# headset.net
KiCad netlist of a schematic drawn in EAGLE
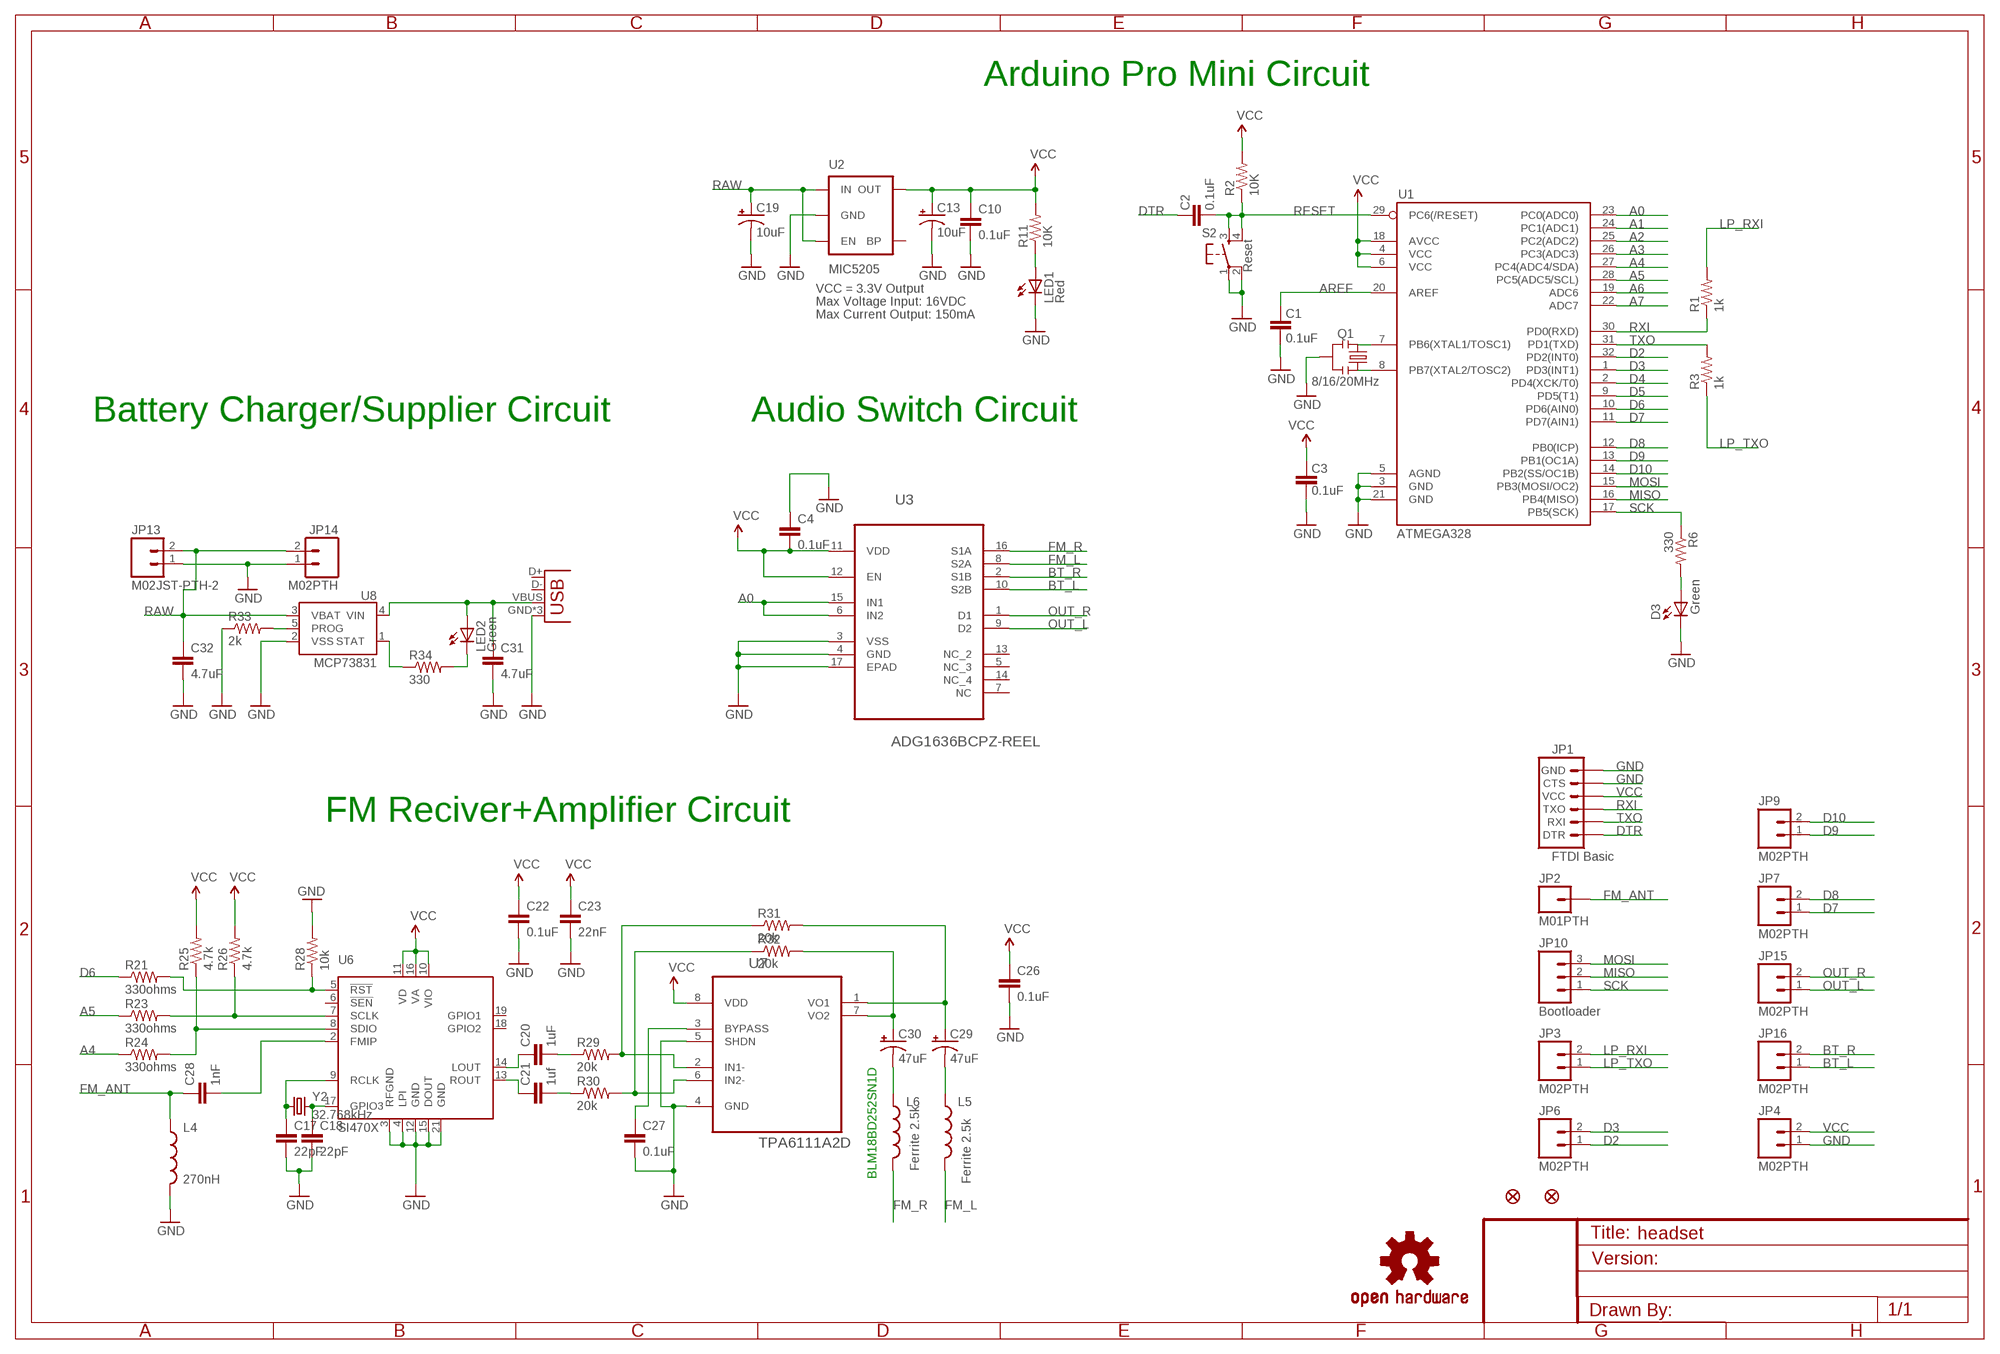
[diagram p0: schematic, sheet 1]

(export (version "E")
  (design (tool "Eeschema 10.0.6"))
  (components
    (comp (ref "C1")
      (value "0.1uF")
      (footprint "eagle-import:0402-CAP")
      (libsource (lib "eagle-import") (part "CAP0402-CAP"))
    )
    (comp (ref "C2")
      (value "0.1uF")
      (footprint "eagle-import:0402-CAP")
      (libsource (lib "eagle-import") (part "CAP0402-CAP"))
    )
    (comp (ref "C3")
      (value "0.1uF")
      (footprint "eagle-import:0402-CAP")
      (libsource (lib "eagle-import") (part "CAP0402-CAP"))
    )
    (comp (ref "C4")
      (value "0.1uF")
      (footprint "eagle-import:0402-CAP")
      (libsource (lib "eagle-import") (part "SparkFun-Passives_CAP0402-CAP"))
    )
    (comp (ref "C10")
      (value "0.1uF")
      (footprint "eagle-import:0402-CAP")
      (libsource (lib "eagle-import") (part "CAP0402-CAP"))
    )
    (comp (ref "C13")
      (value "10uF")
      (footprint "eagle-import:EIA3216")
      (libsource (lib "eagle-import") (part "CAP_POL1206"))
    )
    (comp (ref "C17")
      (value "22pF")
      (footprint "eagle-import:0402-CAP")
      (libsource (lib "eagle-import") (part "SparkFun-Passives_CAP0402-CAP"))
    )
    (comp (ref "C18")
      (value "22pF")
      (footprint "eagle-import:0402-CAP")
      (libsource (lib "eagle-import") (part "SparkFun-Passives_CAP0402-CAP"))
    )
    (comp (ref "C19")
      (value "10uF")
      (footprint "eagle-import:EIA3216")
      (libsource (lib "eagle-import") (part "CAP_POL1206"))
    )
    (comp (ref "C20")
      (value "1uF")
      (footprint "eagle-import:0402-CAP")
      (libsource (lib "eagle-import") (part "SparkFun-Passives_CAP0402-CAP"))
    )
    (comp (ref "C21")
      (value "1uf")
      (footprint "eagle-import:0402-CAP")
      (libsource (lib "eagle-import") (part "SparkFun-Passives_CAP0402-CAP"))
    )
    (comp (ref "C22")
      (value "0.1uF")
      (footprint "eagle-import:0402-CAP")
      (libsource (lib "eagle-import") (part "SparkFun-Passives_CAP0402-CAP"))
    )
    (comp (ref "C23")
      (value "22nF")
      (footprint "eagle-import:0402-CAP")
      (libsource (lib "eagle-import") (part "SparkFun-Passives_CAP0402-CAP"))
    )
    (comp (ref "C26")
      (value "0.1uF")
      (footprint "eagle-import:0402-CAP")
      (libsource (lib "eagle-import") (part "SparkFun-Passives_CAP0402-CAP"))
    )
    (comp (ref "C27")
      (value "0.1uF")
      (footprint "eagle-import:0402-CAP")
      (libsource (lib "eagle-import") (part "SparkFun-Passives_CAP0402-CAP"))
    )
    (comp (ref "C28")
      (value "1nF")
      (footprint "eagle-import:0402-CAP")
      (libsource (lib "eagle-import") (part "SparkFun-Passives_CAP0402-CAP"))
    )
    (comp (ref "C29")
      (value "47uF")
      (footprint "eagle-import:EIA3528")
      (libsource (lib "eagle-import") (part "SparkFun-Passives_CAP_POL3528"))
    )
    (comp (ref "C30")
      (value "47uF")
      (footprint "eagle-import:EIA3528")
      (libsource (lib "eagle-import") (part "SparkFun-Passives_CAP_POL3528"))
    )
    (comp (ref "C31")
      (value "4.7uF")
      (footprint "eagle-import:0402-CAP")
      (libsource (lib "eagle-import") (part "SparkFun-Passives_CAP0402-CAP"))
    )
    (comp (ref "C32")
      (value "4.7uF")
      (footprint "eagle-import:0402-CAP")
      (libsource (lib "eagle-import") (part "SparkFun-Passives_CAP0402-CAP"))
    )
    (comp (ref "D3")
      (value "Green")
      (footprint "eagle-import:LED-0603")
      (libsource (lib "eagle-import") (part "LED0603"))
    )
    (comp (ref "JP1")
      (value "FTDI Basic")
      (footprint "eagle-import:1X06")
      (libsource (lib "eagle-import") (part "ARDUINO_SERIAL_PROGRAMPTH"))
    )
    (comp (ref "JP2")
      (value "M01PTH")
      (footprint "eagle-import:1X01")
      (libsource (lib "eagle-import") (part "M01PTH"))
    )
    (comp (ref "JP3")
      (value "M02PTH")
      (footprint "eagle-import:1X02")
      (libsource (lib "eagle-import") (part "M02PTH"))
    )
    (comp (ref "JP4")
      (value "M02PTH")
      (footprint "eagle-import:1X02")
      (libsource (lib "eagle-import") (part "M02PTH"))
    )
    (comp (ref "JP5")
      (value "FIDUCIALUFIDUCIAL")
      (footprint "eagle-import:MICRO-FIDUCIAL")
      (libsource (lib "eagle-import") (part "FIDUCIALUFIDUCIAL"))
    )
    (comp (ref "JP6")
      (value "M02PTH")
      (footprint "eagle-import:1X02")
      (libsource (lib "eagle-import") (part "M02PTH"))
    )
    (comp (ref "JP7")
      (value "M02PTH")
      (footprint "eagle-import:1X02")
      (libsource (lib "eagle-import") (part "M02PTH"))
    )
    (comp (ref "JP8")
      (value "FIDUCIALUFIDUCIAL")
      (footprint "eagle-import:MICRO-FIDUCIAL")
      (libsource (lib "eagle-import") (part "FIDUCIALUFIDUCIAL"))
    )
    (comp (ref "JP9")
      (value "M02PTH")
      (footprint "eagle-import:1X02")
      (libsource (lib "eagle-import") (part "M02PTH"))
    )
    (comp (ref "JP10")
      (value "Bootloader")
      (footprint "eagle-import:1X03")
      (libsource (lib "eagle-import") (part "M03PTH"))
    )
    (comp (ref "JP12")
      (value "USB-MICROB")
      (footprint "eagle-import:USB-MICROB")
      (libsource (lib "eagle-import") (part "USB-MICROB"))
    )
    (comp (ref "JP13")
      (value "M02JST-PTH-2")
      (footprint "eagle-import:JST-2-PTH")
      (libsource (lib "eagle-import") (part "M02JST-PTH-2"))
    )
    (comp (ref "JP14")
      (value "M02PTH")
      (footprint "eagle-import:1X02")
      (libsource (lib "eagle-import") (part "M02PTH"))
    )
    (comp (ref "JP15")
      (value "M02PTH")
      (footprint "eagle-import:1X02")
      (libsource (lib "eagle-import") (part "M02PTH"))
    )
    (comp (ref "JP16")
      (value "M02PTH")
      (footprint "eagle-import:1X02")
      (libsource (lib "eagle-import") (part "M02PTH"))
    )
    (comp (ref "L4")
      (value "270nH")
      (footprint "eagle-import:C0402")
      (libsource (lib "eagle-import") (part "INDUCTOR0402"))
    )
    (comp (ref "L5")
      (value "Ferrite 2.5k")
      (footprint "eagle-import:C0402")
      (libsource (lib "eagle-import") (part "INDUCTOR0402"))
    )
    (comp (ref "L6")
      (value "Ferrite 2.5k")
      (footprint "eagle-import:C0402")
      (libsource (lib "eagle-import") (part "INDUCTOR0402"))
    )
    (comp (ref "LED1")
      (value "Red")
      (footprint "eagle-import:LED-0603")
      (libsource (lib "eagle-import") (part "LED0603"))
    )
    (comp (ref "LED2")
      (value "Green")
      (footprint "eagle-import:LED3MM-NS")
      (libsource (lib "eagle-import") (part "SparkFun-LED_LED-3MM-NO_SILK"))
    )
    (comp (ref "Q1")
      (value "8/16/20MHz")
      (footprint "eagle-import:RESONATOR-SMD")
      (libsource (lib "eagle-import") (part "RESONATORSMD"))
    )
    (comp (ref "R1")
      (value "1k")
      (footprint "eagle-import:0402-RES")
      (libsource (lib "eagle-import") (part "SparkFun-Passives_RESISTOR0402-RES"))
    )
    (comp (ref "R2")
      (value "10K")
      (footprint "eagle-import:0402-RES")
      (libsource (lib "eagle-import") (part "RESISTOR0402-RES"))
    )
    (comp (ref "R3")
      (value "1k")
      (footprint "eagle-import:0402-RES")
      (libsource (lib "eagle-import") (part "SparkFun-Passives_RESISTOR0402-RES"))
    )
    (comp (ref "R6")
      (value "330")
      (footprint "eagle-import:0402-RES")
      (libsource (lib "eagle-import") (part "RESISTOR0402-RES"))
    )
    (comp (ref "R11")
      (value "10K")
      (footprint "eagle-import:0402-RES")
      (libsource (lib "eagle-import") (part "RESISTOR0402-RES"))
    )
    (comp (ref "R21")
      (value "330ohms")
      (footprint "eagle-import:0402-RES")
      (libsource (lib "eagle-import") (part "SparkFun-Passives_RESISTOR0402-RES"))
    )
    (comp (ref "R23")
      (value "330ohms")
      (footprint "eagle-import:0402-RES")
      (libsource (lib "eagle-import") (part "SparkFun-Passives_RESISTOR0402-RES"))
    )
    (comp (ref "R24")
      (value "330ohms")
      (footprint "eagle-import:0402-RES")
      (libsource (lib "eagle-import") (part "SparkFun-Passives_RESISTOR0402-RES"))
    )
    (comp (ref "R25")
      (value "4.7k")
      (footprint "eagle-import:0402-RES")
      (libsource (lib "eagle-import") (part "SparkFun-Passives_RESISTOR0402-RES"))
    )
    (comp (ref "R26")
      (value "4.7k")
      (footprint "eagle-import:0402-RES")
      (libsource (lib "eagle-import") (part "SparkFun-Passives_RESISTOR0402-RES"))
    )
    (comp (ref "R28")
      (value "10k")
      (footprint "eagle-import:0402-RES")
      (libsource (lib "eagle-import") (part "SparkFun-Passives_RESISTOR0402-RES"))
    )
    (comp (ref "R29")
      (value "20k")
      (footprint "eagle-import:0402-RES")
      (libsource (lib "eagle-import") (part "SparkFun-Passives_RESISTOR0402-RES"))
    )
    (comp (ref "R30")
      (value "20k")
      (footprint "eagle-import:0402-RES")
      (libsource (lib "eagle-import") (part "SparkFun-Passives_RESISTOR0402-RES"))
    )
    (comp (ref "R31")
      (value "20k")
      (footprint "eagle-import:0402-RES")
      (libsource (lib "eagle-import") (part "SparkFun-Passives_RESISTOR0402-RES"))
    )
    (comp (ref "R32")
      (value "20k")
      (footprint "eagle-import:0402-RES")
      (libsource (lib "eagle-import") (part "SparkFun-Passives_RESISTOR0402-RES"))
    )
    (comp (ref "R33")
      (value "2k")
      (footprint "eagle-import:0402-RES")
      (libsource (lib "eagle-import") (part "SparkFun-Passives_RESISTOR0402-RES"))
    )
    (comp (ref "R34")
      (value "330")
      (footprint "eagle-import:0402-RES")
      (libsource (lib "eagle-import") (part "SparkFun-Passives_RESISTOR0402-RES"))
    )
    (comp (ref "S2")
      (value "Reset")
      (footprint "eagle-import:TACTILE_SWITCH_SMD")
      (libsource (lib "eagle-import") (part "TAC_SWITCHSMD"))
    )
    (comp (ref "U$3")
      (value "OSHW-LOGOS")
      (footprint "eagle-import:OSHW-LOGO-S")
      (libsource (lib "eagle-import") (part "OSHW-LOGOS"))
    )
    (comp (ref "U1")
      (value "ATMEGA328")
      (footprint "eagle-import:TQFP32-08")
      (libsource (lib "eagle-import") (part "ATMEGA168"))
    )
    (comp (ref "U2")
      (value "MIC5205")
      (footprint "eagle-import:SOT23-5")
      (libsource (lib "eagle-import") (part "V_REG_LDOSMD"))
    )
    (comp (ref "U3")
      (value "ADG1636BCPZ-REEL")
      (footprint "eagle-import:QFN65P400X400X100-17N")
      (libsource (lib "eagle-import") (part "ADG1636BCPZ-REEL"))
    )
    (comp (ref "U6")
      (value "SI470X")
      (footprint "eagle-import:SI470X")
      (libsource (lib "eagle-import") (part "SI470X"))
    )
    (comp (ref "U7")
      (value "TPA6111A2D")
      (footprint "eagle-import:SOIC127P600X175-8N")
      (libsource (lib "eagle-import") (part "TPA6111A2D"))
    )
    (comp (ref "U8")
      (value "MCP73831")
      (footprint "eagle-import:SOT23-5")
      (libsource (lib "eagle-import") (part "MCP73831"))
    )
    (comp (ref "Y2")
      (value "32.768kHz")
      (footprint "eagle-import:CRYSTAL-32KHZ-SMD")
      (libsource (lib "eagle-import") (part "CRYSTAL32-SMD"))
    )
  )
  (nets
    (net (code "1") (name "/A0") (class "Default")
      (node (ref "U1") (pin "23") (pinfunction "PC0(ADC0)_23") (pintype "bidirectional"))
      (node (ref "U3") (pin "15") (pinfunction "IN1_15") (pintype "input"))
      (node (ref "U3") (pin "6") (pinfunction "IN2_6") (pintype "input"))
    )
    (net (code "2") (name "/A1") (class "Default")
      (node (ref "U1") (pin "24") (pinfunction "PC1(ADC1)_24") (pintype "bidirectional"))
    )
    (net (code "3") (name "/A2") (class "Default")
      (node (ref "U1") (pin "25") (pinfunction "PC2(ADC2)_25") (pintype "bidirectional"))
    )
    (net (code "4") (name "/A3") (class "Default")
      (node (ref "U1") (pin "26") (pinfunction "PC3(ADC3)_26") (pintype "bidirectional"))
    )
    (net (code "5") (name "/A4") (class "Default")
      (node (ref "R24") (pin "1") (pinfunction "1_1") (pintype "passive"))
      (node (ref "U1") (pin "27") (pinfunction "PC4(ADC4/SDA)_27") (pintype "bidirectional"))
    )
    (net (code "6") (name "/A5") (class "Default")
      (node (ref "R23") (pin "1") (pinfunction "1_1") (pintype "passive"))
      (node (ref "U1") (pin "28") (pinfunction "PC5(ADC5/SCL)_28") (pintype "bidirectional"))
    )
    (net (code "7") (name "/A6") (class "Default")
      (node (ref "U1") (pin "19") (pinfunction "ADC6_19") (pintype "bidirectional"))
    )
    (net (code "8") (name "/A7") (class "Default")
      (node (ref "U1") (pin "22") (pinfunction "ADC7_22") (pintype "bidirectional"))
    )
    (net (code "9") (name "/AREF") (class "Default")
      (node (ref "C1") (pin "2") (pinfunction "2_2") (pintype "passive"))
      (node (ref "U1") (pin "20") (pinfunction "AREF_20") (pintype "bidirectional"))
    )
    (net (code "10") (name "/BT_L") (class "Default")
      (node (ref "JP16") (pin "1") (pinfunction "1_1") (pintype "passive"))
      (node (ref "U3") (pin "10") (pinfunction "S2B_10") (pintype "bidirectional"))
    )
    (net (code "11") (name "/BT_R") (class "Default")
      (node (ref "JP16") (pin "2") (pinfunction "2_2") (pintype "passive"))
      (node (ref "U3") (pin "2") (pinfunction "S1B_2") (pintype "bidirectional"))
    )
    (net (code "12") (name "/D2") (class "Default")
      (node (ref "JP6") (pin "1") (pinfunction "1_1") (pintype "passive"))
      (node (ref "U1") (pin "32") (pinfunction "PD2(INT0)_32") (pintype "bidirectional"))
    )
    (net (code "13") (name "/D3") (class "Default")
      (node (ref "JP6") (pin "2") (pinfunction "2_2") (pintype "passive"))
      (node (ref "U1") (pin "1") (pinfunction "PD3(INT1)_1") (pintype "bidirectional"))
    )
    (net (code "14") (name "/D4") (class "Default")
      (node (ref "U1") (pin "2") (pinfunction "PD4(XCK/T0)_2") (pintype "bidirectional"))
    )
    (net (code "15") (name "/D5") (class "Default")
      (node (ref "U1") (pin "9") (pinfunction "PD5(T1)_9") (pintype "bidirectional"))
    )
    (net (code "16") (name "/D6") (class "Default")
      (node (ref "R21") (pin "1") (pinfunction "1_1") (pintype "passive"))
      (node (ref "U1") (pin "10") (pinfunction "PD6(AIN0)_10") (pintype "bidirectional"))
    )
    (net (code "17") (name "/D7") (class "Default")
      (node (ref "JP7") (pin "1") (pinfunction "1_1") (pintype "passive"))
      (node (ref "U1") (pin "11") (pinfunction "PD7(AIN1)_11") (pintype "bidirectional"))
    )
    (net (code "18") (name "/D8") (class "Default")
      (node (ref "JP7") (pin "2") (pinfunction "2_2") (pintype "passive"))
      (node (ref "U1") (pin "12") (pinfunction "PB0(ICP)_12") (pintype "bidirectional"))
    )
    (net (code "19") (name "/D9") (class "Default")
      (node (ref "JP9") (pin "1") (pinfunction "1_1") (pintype "passive"))
      (node (ref "U1") (pin "13") (pinfunction "PB1(OC1A)_13") (pintype "bidirectional"))
    )
    (net (code "20") (name "/D10") (class "Default")
      (node (ref "JP9") (pin "2") (pinfunction "2_2") (pintype "passive"))
      (node (ref "U1") (pin "14") (pinfunction "PB2(SS/OC1B)_14") (pintype "bidirectional"))
    )
    (net (code "21") (name "/DTR") (class "Default")
      (node (ref "C2") (pin "2") (pinfunction "2_2") (pintype "passive"))
      (node (ref "JP1") (pin "1") (pinfunction "DTR_1") (pintype "passive"))
    )
    (net (code "22") (name "/FM_ANT") (class "Default")
      (node (ref "C28") (pin "1") (pinfunction "1_1") (pintype "passive"))
      (node (ref "JP2") (pin "1") (pinfunction "1_1") (pintype "passive"))
      (node (ref "L4") (pin "1") (pinfunction "1_1") (pintype "passive"))
    )
    (net (code "23") (name "/FM_L") (class "Default")
      (node (ref "L5") (pin "2") (pinfunction "2_2") (pintype "passive"))
      (node (ref "U3") (pin "8") (pinfunction "S2A_8") (pintype "bidirectional"))
    )
    (net (code "24") (name "/FM_R") (class "Default")
      (node (ref "L6") (pin "2") (pinfunction "2_2") (pintype "passive"))
      (node (ref "U3") (pin "16") (pinfunction "S1A_16") (pintype "bidirectional"))
    )
    (net (code "25") (name "/LP_RXI") (class "Default")
      (node (ref "JP3") (pin "2") (pinfunction "2_2") (pintype "passive"))
      (node (ref "R1") (pin "2") (pinfunction "2_2") (pintype "passive"))
    )
    (net (code "26") (name "/LP_TXO") (class "Default")
      (node (ref "JP3") (pin "1") (pinfunction "1_1") (pintype "passive"))
      (node (ref "R3") (pin "1") (pinfunction "1_1") (pintype "passive"))
    )
    (net (code "27") (name "/MISO") (class "Default")
      (node (ref "JP10") (pin "2") (pinfunction "2_2") (pintype "passive"))
      (node (ref "U1") (pin "16") (pinfunction "PB4(MISO)_16") (pintype "bidirectional"))
    )
    (net (code "28") (name "/MOSI") (class "Default")
      (node (ref "JP10") (pin "3") (pinfunction "3_3") (pintype "passive"))
      (node (ref "U1") (pin "15") (pinfunction "PB3(MOSI/OC2)_15") (pintype "bidirectional"))
    )
    (net (code "29") (name "/OUT_L") (class "Default")
      (node (ref "JP15") (pin "1") (pinfunction "1_1") (pintype "passive"))
      (node (ref "U3") (pin "9") (pinfunction "D2_9") (pintype "bidirectional"))
    )
    (net (code "30") (name "/OUT_R") (class "Default")
      (node (ref "JP15") (pin "2") (pinfunction "2_2") (pintype "passive"))
      (node (ref "U3") (pin "1") (pinfunction "D1_1") (pintype "bidirectional"))
    )
    (net (code "31") (name "/RAW") (class "Default")
      (node (ref "C19") (pin "A") (pinfunction "+_A") (pintype "passive"))
      (node (ref "C32") (pin "1") (pinfunction "1_1") (pintype "passive"))
      (node (ref "JP13") (pin "2") (pinfunction "2_2") (pintype "passive"))
      (node (ref "JP14") (pin "2") (pinfunction "2_2") (pintype "passive"))
      (node (ref "U2") (pin "1") (pinfunction "IN_1") (pintype "input"))
      (node (ref "U2") (pin "3") (pinfunction "EN_3") (pintype "input"))
      (node (ref "U8") (pin "3") (pinfunction "VBAT_3") (pintype "power_in"))
    )
    (net (code "32") (name "/RESET") (class "Default")
      (node (ref "C2") (pin "1") (pinfunction "1_1") (pintype "passive"))
      (node (ref "R2") (pin "1") (pinfunction "1_1") (pintype "passive"))
      (node (ref "S2") (pin "3") (pinfunction "3_3") (pintype "passive"))
      (node (ref "S2") (pin "4") (pinfunction "4_4") (pintype "passive"))
      (node (ref "U1") (pin "29") (pinfunction "PC6(/RESET)_29") (pintype "bidirectional"))
    )
    (net (code "33") (name "/RXI") (class "Default")
      (node (ref "JP1") (pin "3") (pinfunction "TXO_3") (pintype "passive"))
      (node (ref "R1") (pin "1") (pinfunction "1_1") (pintype "passive"))
      (node (ref "U1") (pin "30") (pinfunction "PD0(RXD)_30") (pintype "bidirectional"))
    )
    (net (code "34") (name "/SCK") (class "Default")
      (node (ref "JP10") (pin "1") (pinfunction "1_1") (pintype "passive"))
      (node (ref "R6") (pin "1") (pinfunction "1_1") (pintype "passive"))
      (node (ref "U1") (pin "17") (pinfunction "PB5(SCK)_17") (pintype "bidirectional"))
    )
    (net (code "35") (name "/TXO") (class "Default")
      (node (ref "JP1") (pin "2") (pinfunction "RXI_2") (pintype "passive"))
      (node (ref "R3") (pin "2") (pinfunction "2_2") (pintype "passive"))
      (node (ref "U1") (pin "31") (pinfunction "PD1(TXD)_31") (pintype "bidirectional"))
    )
    (net (code "36") (name "GND") (class "Default")
      (node (ref "C1") (pin "1") (pinfunction "1_1") (pintype "passive"))
      (node (ref "C10") (pin "2") (pinfunction "2_2") (pintype "passive"))
      (node (ref "C13") (pin "C") (pinfunction "-_C") (pintype "passive"))
      (node (ref "C17") (pin "2") (pinfunction "2_2") (pintype "passive"))
      (node (ref "C18") (pin "2") (pinfunction "2_2") (pintype "passive"))
      (node (ref "C19") (pin "C") (pinfunction "-_C") (pintype "passive"))
      (node (ref "C22") (pin "2") (pinfunction "2_2") (pintype "passive"))
      (node (ref "C23") (pin "2") (pinfunction "2_2") (pintype "passive"))
      (node (ref "C26") (pin "2") (pinfunction "2_2") (pintype "passive"))
      (node (ref "C27") (pin "2") (pinfunction "2_2") (pintype "passive"))
      (node (ref "C3") (pin "1") (pinfunction "1_1") (pintype "passive"))
      (node (ref "C31") (pin "2") (pinfunction "2_2") (pintype "passive"))
      (node (ref "C32") (pin "2") (pinfunction "2_2") (pintype "passive"))
      (node (ref "C4") (pin "1") (pinfunction "1_1") (pintype "passive"))
      (node (ref "D3") (pin "C") (pinfunction "C_C") (pintype "passive"))
      (node (ref "JP1") (pin "5") (pinfunction "CTS_5") (pintype "passive"))
      (node (ref "JP1") (pin "6") (pinfunction "GND_6") (pintype "passive"))
      (node (ref "JP12") (pin "GND") (pinfunction "GND_GND") (pintype "bidirectional"))
      (node (ref "JP12") (pin "MT1") (pinfunction "GND_MT1") (pintype "bidirectional"))
      (node (ref "JP12") (pin "MT2") (pinfunction "GND_MT2") (pintype "bidirectional"))
      (node (ref "JP13") (pin "1") (pinfunction "1_1") (pintype "passive"))
      (node (ref "JP14") (pin "1") (pinfunction "1_1") (pintype "passive"))
      (node (ref "JP4") (pin "1") (pinfunction "1_1") (pintype "passive"))
      (node (ref "L4") (pin "2") (pinfunction "2_2") (pintype "passive"))
      (node (ref "LED1") (pin "C") (pinfunction "C_C") (pintype "passive"))
      (node (ref "Q1") (pin "2") (pinfunction "2_2") (pintype "passive"))
      (node (ref "R28") (pin "2") (pinfunction "2_2") (pintype "passive"))
      (node (ref "R33") (pin "1") (pinfunction "1_1") (pintype "passive"))
      (node (ref "S2") (pin "1") (pinfunction "1_1") (pintype "passive"))
      (node (ref "S2") (pin "2") (pinfunction "2_2") (pintype "passive"))
      (node (ref "U1") (pin "21") (pinfunction "GND_21") (pintype "bidirectional"))
      (node (ref "U1") (pin "3") (pinfunction "GND_3") (pintype "bidirectional"))
      (node (ref "U1") (pin "5") (pinfunction "AGND_5") (pintype "bidirectional"))
      (node (ref "U2") (pin "2") (pinfunction "GND_2") (pintype "input"))
      (node (ref "U3") (pin "17") (pinfunction "EPAD_17") (pintype "passive"))
      (node (ref "U3") (pin "3") (pinfunction "VSS_3") (pintype "power_in"))
      (node (ref "U3") (pin "4") (pinfunction "GND_4") (pintype "passive"))
      (node (ref "U6") (pin "12") (pinfunction "GND_12") (pintype "bidirectional"))
      (node (ref "U6") (pin "15") (pinfunction "DOUT_15") (pintype "bidirectional"))
      (node (ref "U6") (pin "21") (pinfunction "GND_21") (pintype "bidirectional"))
      (node (ref "U6") (pin "3") (pinfunction "RFGND_3") (pintype "bidirectional"))
      (node (ref "U6") (pin "4") (pinfunction "LPI_4") (pintype "bidirectional"))
      (node (ref "U7") (pin "4") (pinfunction "GND_4") (pintype "passive"))
      (node (ref "U7") (pin "5") (pinfunction "SHDN_5") (pintype "input"))
      (node (ref "U8") (pin "2") (pinfunction "VSS_2") (pintype "power_in"))
    )
    (net (code "37") (name "Net-(C20-Pad2)") (class "Default")
      (node (ref "C20") (pin "2") (pinfunction "2_2") (pintype "passive"))
      (node (ref "R29") (pin "1") (pinfunction "1_1") (pintype "passive"))
    )
    (net (code "38") (name "Net-(C21-Pad2)") (class "Default")
      (node (ref "C21") (pin "2") (pinfunction "2_2") (pintype "passive"))
      (node (ref "R30") (pin "1") (pinfunction "1_1") (pintype "passive"))
    )
    (net (code "39") (name "Net-(C29-+)") (class "Default")
      (node (ref "C29") (pin "A") (pinfunction "+_A") (pintype "passive"))
      (node (ref "R31") (pin "2") (pinfunction "2_2") (pintype "passive"))
      (node (ref "U7") (pin "1") (pinfunction "VO1_1") (pintype "output"))
    )
    (net (code "40") (name "Net-(C29--)") (class "Default")
      (node (ref "C29") (pin "C") (pinfunction "-_C") (pintype "passive"))
      (node (ref "L5") (pin "1") (pinfunction "1_1") (pintype "passive"))
    )
    (net (code "41") (name "Net-(C30-+)") (class "Default")
      (node (ref "C30") (pin "A") (pinfunction "+_A") (pintype "passive"))
      (node (ref "R32") (pin "2") (pinfunction "2_2") (pintype "passive"))
      (node (ref "U7") (pin "7") (pinfunction "VO2_7") (pintype "output"))
    )
    (net (code "42") (name "Net-(C30--)") (class "Default")
      (node (ref "C30") (pin "C") (pinfunction "-_C") (pintype "passive"))
      (node (ref "L6") (pin "1") (pinfunction "1_1") (pintype "passive"))
    )
    (net (code "43") (name "Net-(D3-PadA)") (class "Default")
      (node (ref "D3") (pin "A") (pinfunction "A_A") (pintype "passive"))
      (node (ref "R6") (pin "2") (pinfunction "2_2") (pintype "passive"))
    )
    (net (code "44") (name "Net-(LED1-PadA)") (class "Default")
      (node (ref "LED1") (pin "A") (pinfunction "A_A") (pintype "passive"))
      (node (ref "R11") (pin "1") (pinfunction "1_1") (pintype "passive"))
    )
    (net (code "45") (name "Net-(LED2-C)") (class "Default")
      (node (ref "LED2") (pin "K") (pinfunction "C_K") (pintype "passive"))
      (node (ref "R34") (pin "2") (pinfunction "2_2") (pintype "passive"))
    )
    (net (code "46") (name "Net-(U1-PB6(XTAL1{slash}TOSC1))") (class "Default")
      (node (ref "Q1") (pin "3") (pinfunction "3_3") (pintype "passive"))
      (node (ref "U1") (pin "7") (pinfunction "PB6(XTAL1/TOSC1)_7") (pintype "bidirectional"))
    )
    (net (code "47") (name "Net-(U1-PB7(XTAL2{slash}TOSC2))") (class "Default")
      (node (ref "Q1") (pin "1") (pinfunction "1_1") (pintype "passive"))
      (node (ref "U1") (pin "8") (pinfunction "PB7(XTAL2/TOSC2)_8") (pintype "bidirectional"))
    )
    (net (code "48") (name "Net-(U6-FMIP)") (class "Default")
      (node (ref "C28") (pin "2") (pinfunction "2_2") (pintype "passive"))
      (node (ref "U6") (pin "2") (pinfunction "FMIP_2") (pintype "bidirectional"))
    )
    (net (code "49") (name "Net-(U6-GPIO3)") (class "Default")
      (node (ref "C18") (pin "1") (pinfunction "1_1") (pintype "passive"))
      (node (ref "U6") (pin "17") (pinfunction "GPIO3_17") (pintype "bidirectional"))
      (node (ref "Y2") (pin "X2") (pinfunction "2_X2") (pintype "passive"))
    )
    (net (code "50") (name "Net-(U6-LOUT)") (class "Default")
      (node (ref "C20") (pin "1") (pinfunction "1_1") (pintype "passive"))
      (node (ref "U6") (pin "14") (pinfunction "LOUT_14") (pintype "bidirectional"))
    )
    (net (code "51") (name "Net-(U6-RCLK)") (class "Default")
      (node (ref "C17") (pin "1") (pinfunction "1_1") (pintype "passive"))
      (node (ref "U6") (pin "9") (pinfunction "RCLK_9") (pintype "bidirectional"))
      (node (ref "Y2") (pin "X1") (pinfunction "1_X1") (pintype "passive"))
    )
    (net (code "52") (name "Net-(U6-ROUT)") (class "Default")
      (node (ref "C21") (pin "1") (pinfunction "1_1") (pintype "passive"))
      (node (ref "U6") (pin "13") (pinfunction "ROUT_13") (pintype "bidirectional"))
    )
    (net (code "53") (name "Net-(U6-SCLK)") (class "Default")
      (node (ref "R23") (pin "2") (pinfunction "2_2") (pintype "passive"))
      (node (ref "R26") (pin "1") (pinfunction "1_1") (pintype "passive"))
      (node (ref "U6") (pin "7") (pinfunction "SCLK_7") (pintype "bidirectional"))
    )
    (net (code "54") (name "Net-(U6-SDIO)") (class "Default")
      (node (ref "R24") (pin "2") (pinfunction "2_2") (pintype "passive"))
      (node (ref "R25") (pin "1") (pinfunction "1_1") (pintype "passive"))
      (node (ref "U6") (pin "8") (pinfunction "SDIO_8") (pintype "bidirectional"))
    )
    (net (code "55") (name "Net-(U6-~{RST})") (class "Default")
      (node (ref "R21") (pin "2") (pinfunction "2_2") (pintype "passive"))
      (node (ref "R28") (pin "1") (pinfunction "1_1") (pintype "passive"))
      (node (ref "U6") (pin "5") (pinfunction "~{RST}_5") (pintype "bidirectional"))
    )
    (net (code "56") (name "Net-(U7-BYPASS)") (class "Default")
      (node (ref "C27") (pin "1") (pinfunction "1_1") (pintype "passive"))
      (node (ref "U7") (pin "3") (pinfunction "BYPASS_3") (pintype "passive"))
    )
    (net (code "57") (name "Net-(U7-IN1-)") (class "Default")
      (node (ref "R29") (pin "2") (pinfunction "2_2") (pintype "passive"))
      (node (ref "R31") (pin "1") (pinfunction "1_1") (pintype "passive"))
      (node (ref "U7") (pin "2") (pinfunction "IN1-_2") (pintype "input"))
    )
    (net (code "58") (name "Net-(U7-IN2-)") (class "Default")
      (node (ref "R30") (pin "2") (pinfunction "2_2") (pintype "passive"))
      (node (ref "R32") (pin "1") (pinfunction "1_1") (pintype "passive"))
      (node (ref "U7") (pin "6") (pinfunction "IN2-_6") (pintype "input"))
    )
    (net (code "59") (name "Net-(U8-PROG)") (class "Default")
      (node (ref "R33") (pin "2") (pinfunction "2_2") (pintype "passive"))
      (node (ref "U8") (pin "5") (pinfunction "PROG_5") (pintype "input"))
    )
    (net (code "60") (name "Net-(U8-STAT)") (class "Default")
      (node (ref "R34") (pin "1") (pinfunction "1_1") (pintype "passive"))
      (node (ref "U8") (pin "1") (pinfunction "STAT_1") (pintype "output"))
    )
    (net (code "61") (name "Net-(U8-VIN)") (class "Default")
      (node (ref "C31") (pin "1") (pinfunction "1_1") (pintype "passive"))
      (node (ref "JP12") (pin "VBUS") (pinfunction "VBUS_VBUS") (pintype "bidirectional"))
      (node (ref "LED2") (pin "A") (pinfunction "A_A") (pintype "passive"))
      (node (ref "U8") (pin "4") (pinfunction "VIN_4") (pintype "power_in"))
    )
    (net (code "62") (name "VCC") (class "Default")
      (node (ref "C10") (pin "1") (pinfunction "1_1") (pintype "passive"))
      (node (ref "C13") (pin "A") (pinfunction "+_A") (pintype "passive"))
      (node (ref "C22") (pin "1") (pinfunction "1_1") (pintype "passive"))
      (node (ref "C23") (pin "1") (pinfunction "1_1") (pintype "passive"))
      (node (ref "C26") (pin "1") (pinfunction "1_1") (pintype "passive"))
      (node (ref "C3") (pin "2") (pinfunction "2_2") (pintype "passive"))
      (node (ref "C4") (pin "2") (pinfunction "2_2") (pintype "passive"))
      (node (ref "JP1") (pin "4") (pinfunction "VCC_4") (pintype "passive"))
      (node (ref "JP4") (pin "2") (pinfunction "2_2") (pintype "passive"))
      (node (ref "R11") (pin "2") (pinfunction "2_2") (pintype "passive"))
      (node (ref "R2") (pin "2") (pinfunction "2_2") (pintype "passive"))
      (node (ref "R25") (pin "2") (pinfunction "2_2") (pintype "passive"))
      (node (ref "R26") (pin "2") (pinfunction "2_2") (pintype "passive"))
      (node (ref "U1") (pin "18") (pinfunction "AVCC_18") (pintype "bidirectional"))
      (node (ref "U1") (pin "4") (pinfunction "VCC_4") (pintype "bidirectional"))
      (node (ref "U1") (pin "6") (pinfunction "VCC_6") (pintype "bidirectional"))
      (node (ref "U2") (pin "5") (pinfunction "OUT_5") (pintype "passive"))
      (node (ref "U3") (pin "11") (pinfunction "VDD_11") (pintype "power_in"))
      (node (ref "U3") (pin "12") (pinfunction "EN_12") (pintype "input"))
      (node (ref "U6") (pin "10") (pinfunction "VIO_10") (pintype "bidirectional"))
      (node (ref "U6") (pin "11") (pinfunction "VD_11") (pintype "bidirectional"))
      (node (ref "U6") (pin "16") (pinfunction "VA_16") (pintype "bidirectional"))
      (node (ref "U7") (pin "8") (pinfunction "VDD_8") (pintype "power_in"))
    )
    (net (code "63") (name "unconnected-(JP12-PadD+)") (class "Default")
      (node (ref "JP12") (pin "D+") (pinfunction "D+_D+") (pintype "bidirectional"))
    )
    (net (code "64") (name "unconnected-(JP12-PadD-)") (class "Default")
      (node (ref "JP12") (pin "D-") (pinfunction "D-_D-") (pintype "bidirectional"))
    )
    (net (code "65") (name "unconnected-(U2-BP-Pad4)") (class "Default")
      (node (ref "U2") (pin "4") (pinfunction "BP_4") (pintype "input"))
    )
    (net (code "66") (name "unconnected-(U3-NC-Pad7)") (class "Default")
      (node (ref "U3") (pin "7") (pinfunction "NC_7") (pintype "no_connect"))
    )
    (net (code "67") (name "unconnected-(U3-NC_2-Pad13)") (class "Default")
      (node (ref "U3") (pin "13") (pinfunction "NC_2_13") (pintype "no_connect"))
    )
    (net (code "68") (name "unconnected-(U3-NC_3-Pad5)") (class "Default")
      (node (ref "U3") (pin "5") (pinfunction "NC_3_5") (pintype "no_connect"))
    )
    (net (code "69") (name "unconnected-(U3-NC_4-Pad14)") (class "Default")
      (node (ref "U3") (pin "14") (pinfunction "NC_4_14") (pintype "no_connect"))
    )
    (net (code "70") (name "unconnected-(U6-GPIO1-Pad19)") (class "Default")
      (node (ref "U6") (pin "19") (pinfunction "GPIO1_19") (pintype "bidirectional"))
    )
    (net (code "71") (name "unconnected-(U6-GPIO2-Pad18)") (class "Default")
      (node (ref "U6") (pin "18") (pinfunction "GPIO2_18") (pintype "bidirectional"))
    )
    (net (code "72") (name "unconnected-(U6-~{SEN}-Pad6)") (class "Default")
      (node (ref "U6") (pin "6") (pinfunction "~{SEN}_6") (pintype "bidirectional"))
    )
  )
)
